# RC_Filter.net
KiCad netlist of a schematic drawn in Altium Designer
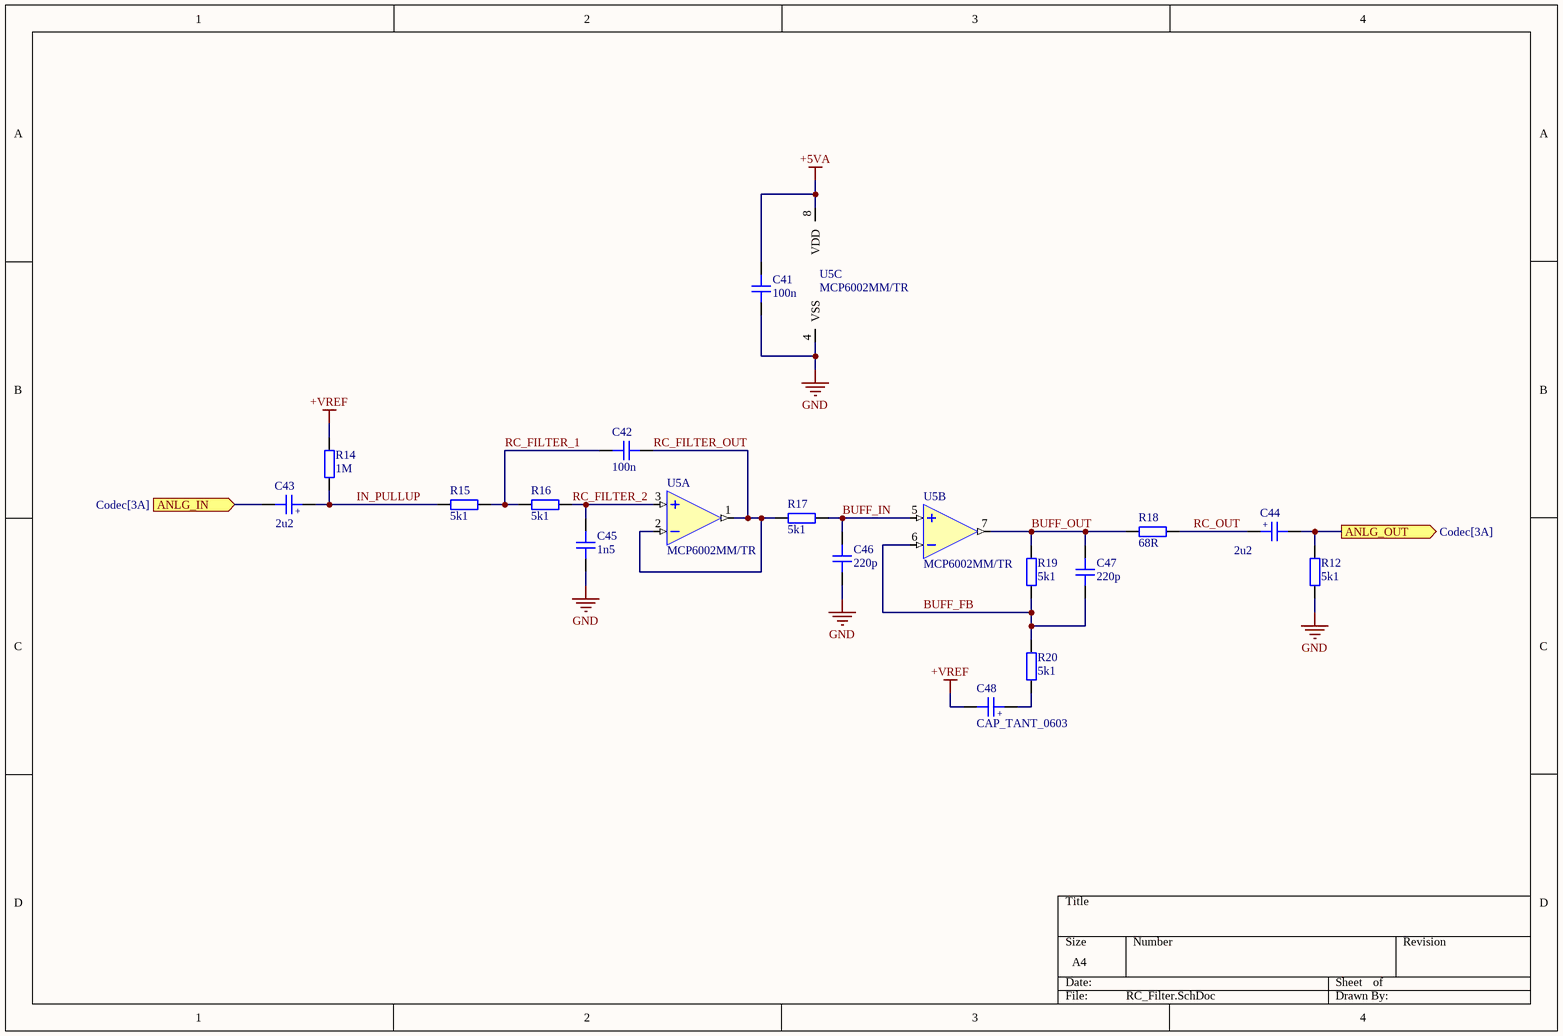
[diagram p0: RC_Filter.SchDoc]

(export (version "E")
  (design (tool "Eeschema 10.0.6"))
  (components
    (comp (ref "C41")
      (value "100n")
      (footprint "CAP_0603")
      (description "Capacitor SMD 0603")
      (libsource (lib "Schematic-Lib-PhilsLab") (part "CAP_0603"))
    )
    (comp (ref "C42")
      (value "100n")
      (footprint "CAP_0603")
      (description "Capacitor SMD 0603")
      (libsource (lib "Schematic-Lib-PhilsLab") (part "CAP_0603"))
    )
    (comp (ref "C43")
      (value "2u2")
      (footprint "CAP_TANT_0603")
      (description "Capacitor SMD Tantalum 0603")
      (libsource (lib "Schematic-Lib-PhilsLab") (part "CAP_TANT_0603"))
    )
    (comp (ref "C44")
      (value "2u2")
      (footprint "CAP_TANT_0603")
      (description "Capacitor SMD Tantalum 0603")
      (libsource (lib "Schematic-Lib-PhilsLab") (part "CAP_TANT_0603"))
    )
    (comp (ref "C45")
      (value "1n5")
      (footprint "CAP_0603")
      (description "Capacitor SMD 0603")
      (libsource (lib "Schematic-Lib-PhilsLab") (part "CAP_0603"))
    )
    (comp (ref "C46")
      (value "220p")
      (footprint "CAP_0603")
      (description "Capacitor SMD 0603")
      (libsource (lib "Schematic-Lib-PhilsLab") (part "CAP_0603"))
    )
    (comp (ref "C47")
      (value "220p")
      (footprint "CAP_0603")
      (description "Capacitor SMD 0603")
      (libsource (lib "Schematic-Lib-PhilsLab") (part "CAP_0603"))
    )
    (comp (ref "C48")
      (value "CAP_TANT_0603")
      (footprint "CAP_TANT_0603")
      (description "Capacitor SMD Tantalum 0603")
      (libsource (lib "Schematic-Lib-PhilsLab") (part "CAP_TANT_0603"))
    )
    (comp (ref "R12")
      (value "5k1")
      (footprint "RES_0603")
      (description "Resistor SMD 0603")
      (libsource (lib "Schematic-Lib-PhilsLab") (part "RES_0603"))
    )
    (comp (ref "R14")
      (value "1M")
      (footprint "RES_0603")
      (description "Resistor SMD 0603")
      (libsource (lib "Schematic-Lib-PhilsLab") (part "RES_0603"))
    )
    (comp (ref "R15")
      (value "5k1")
      (footprint "RES_0603")
      (description "Resistor SMD 0603")
      (libsource (lib "Schematic-Lib-PhilsLab") (part "RES_0603"))
    )
    (comp (ref "R16")
      (value "5k1")
      (footprint "RES_0603")
      (description "Resistor SMD 0603")
      (libsource (lib "Schematic-Lib-PhilsLab") (part "RES_0603"))
    )
    (comp (ref "R17")
      (value "5k1")
      (footprint "RES_0603")
      (description "Resistor SMD 0603")
      (libsource (lib "Schematic-Lib-PhilsLab") (part "RES_0603"))
    )
    (comp (ref "R18")
      (value "68R")
      (footprint "RES_0603")
      (description "Resistor SMD 0603")
      (libsource (lib "Schematic-Lib-PhilsLab") (part "RES_0603"))
    )
    (comp (ref "R19")
      (value "5k1")
      (footprint "RES_0603")
      (description "Resistor SMD 0603")
      (libsource (lib "Schematic-Lib-PhilsLab") (part "RES_0603"))
    )
    (comp (ref "R20")
      (value "5k1")
      (footprint "RES_0603")
      (description "Resistor SMD 0603")
      (libsource (lib "Schematic-Lib-PhilsLab") (part "RES_0603"))
    )
    (comp (ref "U5")
      (value "MCP6002MM/TR")
      (footprint "MSOP8")
      (description "1MHZ CMOS Rail-to-Rail IO Opamp with RF Filter MSOP-8")
      (fields (field (name "MANUFACTURER") "HGSEMI"))
      (libsource (lib "Schematic-Lib-PhilsLab") (part "MCP6002MM/TR"))
    )
  )
  (nets
    (net (code "1") (name "+5VA") (class "Default")
      (node (ref "C41") (pin "2") (pinfunction "2_2") (pintype "passive"))
      (node (ref "U5") (pin "8") (pinfunction "VDD_8") (pintype "passive"))
    )
    (net (code "2") (name "+VREF") (class "Default")
      (node (ref "C48") (pin "K") (pinfunction "K_K") (pintype "passive"))
      (node (ref "R14") (pin "2") (pinfunction "2_2") (pintype "passive"))
    )
    (net (code "3") (name "/ANLG_IN") (class "Default")
      (node (ref "C43") (pin "K") (pinfunction "K_K") (pintype "passive"))
    )
    (net (code "4") (name "/ANLG_OUT") (class "Default")
      (node (ref "C44") (pin "K") (pinfunction "K_K") (pintype "passive"))
      (node (ref "R12") (pin "1") (pinfunction "1_1") (pintype "passive"))
    )
    (net (code "5") (name "/BUFF_FB") (class "Default")
      (node (ref "C47") (pin "2") (pinfunction "2_2") (pintype "passive"))
      (node (ref "R19") (pin "2") (pinfunction "2_2") (pintype "passive"))
      (node (ref "R20") (pin "1") (pinfunction "1_1") (pintype "passive"))
      (node (ref "U5") (pin "6") (pinfunction "2IN-_6") (pintype "input"))
    )
    (net (code "6") (name "/BUFF_IN") (class "Default")
      (node (ref "C46") (pin "1") (pinfunction "1_1") (pintype "passive"))
      (node (ref "R17") (pin "1") (pinfunction "1_1") (pintype "passive"))
      (node (ref "U5") (pin "5") (pinfunction "2IN+_5") (pintype "input"))
    )
    (net (code "7") (name "/BUFF_OUT") (class "Default")
      (node (ref "C47") (pin "1") (pinfunction "1_1") (pintype "passive"))
      (node (ref "R18") (pin "2") (pinfunction "2_2") (pintype "passive"))
      (node (ref "R19") (pin "1") (pinfunction "1_1") (pintype "passive"))
      (node (ref "U5") (pin "7") (pinfunction "2OUT_7") (pintype "output"))
    )
    (net (code "8") (name "/IN_PULLUP") (class "Default")
      (node (ref "C43") (pin "A") (pinfunction "A_A") (pintype "passive"))
      (node (ref "R14") (pin "1") (pinfunction "1_1") (pintype "passive"))
      (node (ref "R15") (pin "2") (pinfunction "2_2") (pintype "passive"))
    )
    (net (code "9") (name "/RC_FILTER_1") (class "Default")
      (node (ref "C42") (pin "1") (pinfunction "1_1") (pintype "passive"))
      (node (ref "R15") (pin "1") (pinfunction "1_1") (pintype "passive"))
      (node (ref "R16") (pin "2") (pinfunction "2_2") (pintype "passive"))
    )
    (net (code "10") (name "/RC_FILTER_2") (class "Default")
      (node (ref "C45") (pin "1") (pinfunction "1_1") (pintype "passive"))
      (node (ref "R16") (pin "1") (pinfunction "1_1") (pintype "passive"))
      (node (ref "U5") (pin "3") (pinfunction "1IN+_3") (pintype "input"))
    )
    (net (code "11") (name "/RC_FILTER_OUT") (class "Default")
      (node (ref "C42") (pin "2") (pinfunction "2_2") (pintype "passive"))
      (node (ref "R17") (pin "2") (pinfunction "2_2") (pintype "passive"))
      (node (ref "U5") (pin "1") (pinfunction "1OUT_1") (pintype "output"))
      (node (ref "U5") (pin "2") (pinfunction "1IN-_2") (pintype "input"))
    )
    (net (code "12") (name "/RC_OUT") (class "Default")
      (node (ref "C44") (pin "A") (pinfunction "A_A") (pintype "passive"))
      (node (ref "R18") (pin "1") (pinfunction "1_1") (pintype "passive"))
    )
    (net (code "13") (name "GND") (class "Default")
      (node (ref "C41") (pin "1") (pinfunction "1_1") (pintype "passive"))
      (node (ref "C45") (pin "2") (pinfunction "2_2") (pintype "passive"))
      (node (ref "C46") (pin "2") (pinfunction "2_2") (pintype "passive"))
      (node (ref "R12") (pin "2") (pinfunction "2_2") (pintype "passive"))
      (node (ref "U5") (pin "4") (pinfunction "VSS_4") (pintype "passive"))
    )
    (net (code "14") (name "Net-(C48-PadA)") (class "Default")
      (node (ref "C48") (pin "A") (pinfunction "A_A") (pintype "passive"))
      (node (ref "R20") (pin "2") (pinfunction "2_2") (pintype "passive"))
    )
  )
)
